# FanRegulator.net
KiCad netlist of a schematic drawn in EAGLE
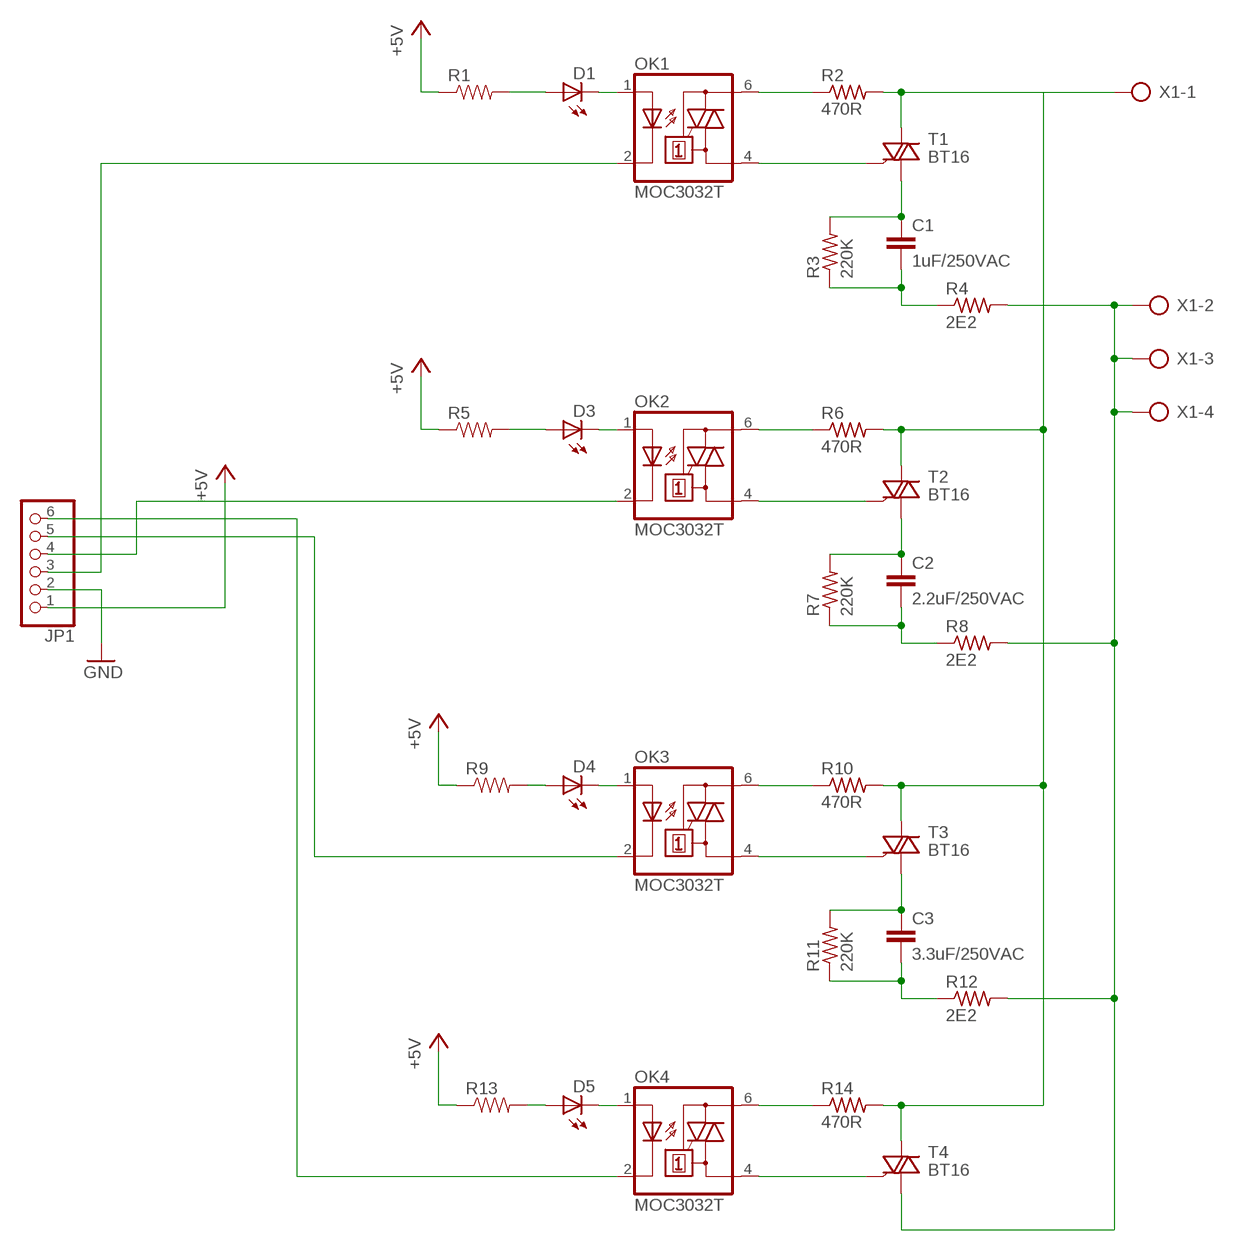
[diagram p0: schematic, sheet 1]

(export (version "E")
  (design (tool "Eeschema 10.0.6"))
  (components
    (comp (ref "C1")
      (value "1uF/250VAC")
      (footprint "eagle-import:C27.5B9")
      (libsource (lib "eagle-import") (part "C27/9"))
    )
    (comp (ref "C2")
      (value "2.2uF/250VAC")
      (footprint "eagle-import:C27.5B9")
      (libsource (lib "eagle-import") (part "C27/9"))
    )
    (comp (ref "C3")
      (value "3.3uF/250VAC")
      (footprint "eagle-import:C27.5B9")
      (libsource (lib "eagle-import") (part "C27/9"))
    )
    (comp (ref "D1")
      (value "LED3MM")
      (footprint "eagle-import:LED3MM")
      (libsource (lib "eagle-import") (part "LED3MM"))
    )
    (comp (ref "D3")
      (value "LED3MM")
      (footprint "eagle-import:LED3MM")
      (libsource (lib "eagle-import") (part "LED3MM"))
    )
    (comp (ref "D4")
      (value "LED3MM")
      (footprint "eagle-import:LED3MM")
      (libsource (lib "eagle-import") (part "LED3MM"))
    )
    (comp (ref "D5")
      (value "LED3MM")
      (footprint "eagle-import:LED3MM")
      (libsource (lib "eagle-import") (part "LED3MM"))
    )
    (comp (ref "JP1")
      (value "PINHD-1X6")
      (footprint "eagle-import:1X06")
      (libsource (lib "eagle-import") (part "PINHD-1X6"))
    )
    (comp (ref "OK1")
      (value "MOC3032T")
      (footprint "eagle-import:DIL06B")
      (libsource (lib "eagle-import") (part "MOC30T32"))
    )
    (comp (ref "OK2")
      (value "MOC3032T")
      (footprint "eagle-import:DIL06B")
      (libsource (lib "eagle-import") (part "MOC30T32"))
    )
    (comp (ref "OK3")
      (value "MOC3032T")
      (footprint "eagle-import:DIL06B")
      (libsource (lib "eagle-import") (part "MOC30T32"))
    )
    (comp (ref "OK4")
      (value "MOC3032T")
      (footprint "eagle-import:DIL06B")
      (libsource (lib "eagle-import") (part "MOC30T32"))
    )
    (comp (ref "R1")
      (value "RESISTOR1206")
      (footprint "eagle-import:1206")
      (libsource (lib "eagle-import") (part "RESISTOR1206"))
    )
    (comp (ref "R2")
      (value "470R")
      (footprint "eagle-import:R0207_1V")
      (libsource (lib "eagle-import") (part "6MM.1"))
    )
    (comp (ref "R3")
      (value "220K")
      (footprint "eagle-import:R0207_1V")
      (libsource (lib "eagle-import") (part "6MM.1"))
    )
    (comp (ref "R4")
      (value "2E2")
      (footprint "eagle-import:R0207_1V")
      (libsource (lib "eagle-import") (part "6MM.1"))
    )
    (comp (ref "R5")
      (value "RESISTOR1206")
      (footprint "eagle-import:1206")
      (libsource (lib "eagle-import") (part "RESISTOR1206"))
    )
    (comp (ref "R6")
      (value "470R")
      (footprint "eagle-import:R0207_1V")
      (libsource (lib "eagle-import") (part "6MM.1"))
    )
    (comp (ref "R7")
      (value "220K")
      (footprint "eagle-import:R0207_1V")
      (libsource (lib "eagle-import") (part "6MM.1"))
    )
    (comp (ref "R8")
      (value "2E2")
      (footprint "eagle-import:R0207_1V")
      (libsource (lib "eagle-import") (part "6MM.1"))
    )
    (comp (ref "R9")
      (value "RESISTOR1206")
      (footprint "eagle-import:1206")
      (libsource (lib "eagle-import") (part "RESISTOR1206"))
    )
    (comp (ref "R10")
      (value "470R")
      (footprint "eagle-import:R0207_1V")
      (libsource (lib "eagle-import") (part "6MM.1"))
    )
    (comp (ref "R11")
      (value "220K")
      (footprint "eagle-import:R0207_1V")
      (libsource (lib "eagle-import") (part "6MM.1"))
    )
    (comp (ref "R12")
      (value "2E2")
      (footprint "eagle-import:R0207_1V")
      (libsource (lib "eagle-import") (part "6MM.1"))
    )
    (comp (ref "R13")
      (value "RESISTOR1206")
      (footprint "eagle-import:1206")
      (libsource (lib "eagle-import") (part "RESISTOR1206"))
    )
    (comp (ref "R14")
      (value "470R")
      (footprint "eagle-import:R0207_1V")
      (libsource (lib "eagle-import") (part "6MM.1"))
    )
    (comp (ref "T1")
      (value "BT16")
      (footprint "eagle-import:TO220BV")
      (libsource (lib "eagle-import") (part "BT138-V"))
    )
    (comp (ref "T2")
      (value "BT16")
      (footprint "eagle-import:TO220BV")
      (libsource (lib "eagle-import") (part "BT138-V"))
    )
    (comp (ref "T3")
      (value "BT16")
      (footprint "eagle-import:TO220BV")
      (libsource (lib "eagle-import") (part "BT138-V"))
    )
    (comp (ref "T4")
      (value "BT16")
      (footprint "eagle-import:TO220BV")
      (libsource (lib "eagle-import") (part "BT138-V"))
    )
    (comp (ref "X1")
      (value "AK300/4")
      (footprint "eagle-import:AK300_4")
      (libsource (lib "eagle-import") (part "AK300/4"))
    )
  )
  (nets
    (net (code "1") (name "+5V") (class "Default")
      (node (ref "JP1") (pin "1") (pinfunction "1_1") (pintype "passive"))
      (node (ref "R1") (pin "1") (pinfunction "1_1") (pintype "passive"))
      (node (ref "R13") (pin "1") (pinfunction "1_1") (pintype "passive"))
      (node (ref "R5") (pin "1") (pinfunction "1_1") (pintype "passive"))
      (node (ref "R9") (pin "1") (pinfunction "1_1") (pintype "passive"))
    )
    (net (code "2") (name "GND") (class "Default")
      (node (ref "JP1") (pin "2") (pinfunction "2_2") (pintype "passive"))
    )
    (net (code "3") (name "Net-(C1-Pad2)") (class "Default")
      (node (ref "C1") (pin "2") (pinfunction "2_2") (pintype "passive"))
      (node (ref "R3") (pin "1") (pinfunction "1_1") (pintype "passive"))
      (node (ref "R4") (pin "1") (pinfunction "1_1") (pintype "passive"))
    )
    (net (code "4") (name "Net-(C2-Pad2)") (class "Default")
      (node (ref "C2") (pin "2") (pinfunction "2_2") (pintype "passive"))
      (node (ref "R7") (pin "1") (pinfunction "1_1") (pintype "passive"))
      (node (ref "R8") (pin "1") (pinfunction "1_1") (pintype "passive"))
    )
    (net (code "5") (name "Net-(C3-Pad2)") (class "Default")
      (node (ref "C3") (pin "2") (pinfunction "2_2") (pintype "passive"))
      (node (ref "R11") (pin "1") (pinfunction "1_1") (pintype "passive"))
      (node (ref "R12") (pin "1") (pinfunction "1_1") (pintype "passive"))
    )
    (net (code "6") (name "Net-(D1-C)") (class "Default")
      (node (ref "D1") (pin "K") (pinfunction "C_K") (pintype "passive"))
      (node (ref "OK1") (pin "1") (pinfunction "A_1") (pintype "passive"))
    )
    (net (code "7") (name "Net-(D1-PadA)") (class "Default")
      (node (ref "D1") (pin "A") (pinfunction "A_A") (pintype "passive"))
      (node (ref "R1") (pin "2") (pinfunction "2_2") (pintype "passive"))
    )
    (net (code "8") (name "Net-(D3-C)") (class "Default")
      (node (ref "D3") (pin "K") (pinfunction "C_K") (pintype "passive"))
      (node (ref "OK2") (pin "1") (pinfunction "A_1") (pintype "passive"))
    )
    (net (code "9") (name "Net-(D3-PadA)") (class "Default")
      (node (ref "D3") (pin "A") (pinfunction "A_A") (pintype "passive"))
      (node (ref "R5") (pin "2") (pinfunction "2_2") (pintype "passive"))
    )
    (net (code "10") (name "Net-(D4-C)") (class "Default")
      (node (ref "D4") (pin "K") (pinfunction "C_K") (pintype "passive"))
      (node (ref "OK3") (pin "1") (pinfunction "A_1") (pintype "passive"))
    )
    (net (code "11") (name "Net-(D4-PadA)") (class "Default")
      (node (ref "D4") (pin "A") (pinfunction "A_A") (pintype "passive"))
      (node (ref "R9") (pin "2") (pinfunction "2_2") (pintype "passive"))
    )
    (net (code "12") (name "Net-(D5-C)") (class "Default")
      (node (ref "D5") (pin "K") (pinfunction "C_K") (pintype "passive"))
      (node (ref "OK4") (pin "1") (pinfunction "A_1") (pintype "passive"))
    )
    (net (code "13") (name "Net-(D5-PadA)") (class "Default")
      (node (ref "D5") (pin "A") (pinfunction "A_A") (pintype "passive"))
      (node (ref "R13") (pin "2") (pinfunction "2_2") (pintype "passive"))
    )
    (net (code "14") (name "Net-(OK1-A1)") (class "Default")
      (node (ref "OK1") (pin "4") (pinfunction "A1_4") (pintype "passive"))
      (node (ref "T1") (pin "G") (pinfunction "G_G") (pintype "passive"))
    )
    (net (code "15") (name "Net-(OK1-A2)") (class "Default")
      (node (ref "OK1") (pin "6") (pinfunction "A2_6") (pintype "passive"))
      (node (ref "R2") (pin "1") (pinfunction "1_1") (pintype "passive"))
    )
    (net (code "16") (name "Net-(OK1-C)") (class "Default")
      (node (ref "JP1") (pin "3") (pinfunction "3_3") (pintype "passive"))
      (node (ref "OK1") (pin "2") (pinfunction "C_2") (pintype "passive"))
    )
    (net (code "17") (name "Net-(OK2-A1)") (class "Default")
      (node (ref "OK2") (pin "4") (pinfunction "A1_4") (pintype "passive"))
      (node (ref "T2") (pin "G") (pinfunction "G_G") (pintype "passive"))
    )
    (net (code "18") (name "Net-(OK2-A2)") (class "Default")
      (node (ref "OK2") (pin "6") (pinfunction "A2_6") (pintype "passive"))
      (node (ref "R6") (pin "1") (pinfunction "1_1") (pintype "passive"))
    )
    (net (code "19") (name "Net-(OK2-C)") (class "Default")
      (node (ref "JP1") (pin "4") (pinfunction "4_4") (pintype "passive"))
      (node (ref "OK2") (pin "2") (pinfunction "C_2") (pintype "passive"))
    )
    (net (code "20") (name "Net-(OK3-A1)") (class "Default")
      (node (ref "OK3") (pin "4") (pinfunction "A1_4") (pintype "passive"))
      (node (ref "T3") (pin "G") (pinfunction "G_G") (pintype "passive"))
    )
    (net (code "21") (name "Net-(OK3-A2)") (class "Default")
      (node (ref "OK3") (pin "6") (pinfunction "A2_6") (pintype "passive"))
      (node (ref "R10") (pin "1") (pinfunction "1_1") (pintype "passive"))
    )
    (net (code "22") (name "Net-(OK3-C)") (class "Default")
      (node (ref "JP1") (pin "5") (pinfunction "5_5") (pintype "passive"))
      (node (ref "OK3") (pin "2") (pinfunction "C_2") (pintype "passive"))
    )
    (net (code "23") (name "Net-(OK4-A1)") (class "Default")
      (node (ref "OK4") (pin "4") (pinfunction "A1_4") (pintype "passive"))
      (node (ref "T4") (pin "G") (pinfunction "G_G") (pintype "passive"))
    )
    (net (code "24") (name "Net-(OK4-A2)") (class "Default")
      (node (ref "OK4") (pin "6") (pinfunction "A2_6") (pintype "passive"))
      (node (ref "R14") (pin "1") (pinfunction "1_1") (pintype "passive"))
    )
    (net (code "25") (name "Net-(OK4-C)") (class "Default")
      (node (ref "JP1") (pin "6") (pinfunction "6_6") (pintype "passive"))
      (node (ref "OK4") (pin "2") (pinfunction "C_2") (pintype "passive"))
    )
    (net (code "26") (name "Net-(T1-A1)") (class "Default")
      (node (ref "C1") (pin "1") (pinfunction "1_1") (pintype "passive"))
      (node (ref "R3") (pin "2") (pinfunction "2_2") (pintype "passive"))
      (node (ref "T1") (pin "T1") (pinfunction "A1_T1") (pintype "passive"))
    )
    (net (code "27") (name "Net-(T1-A2)") (class "Default")
      (node (ref "R10") (pin "2") (pinfunction "2_2") (pintype "passive"))
      (node (ref "R14") (pin "2") (pinfunction "2_2") (pintype "passive"))
      (node (ref "R2") (pin "2") (pinfunction "2_2") (pintype "passive"))
      (node (ref "R6") (pin "2") (pinfunction "2_2") (pintype "passive"))
      (node (ref "T1") (pin "T2") (pinfunction "A2_T2") (pintype "passive"))
      (node (ref "T2") (pin "T2") (pinfunction "A2_T2") (pintype "passive"))
      (node (ref "T3") (pin "T2") (pinfunction "A2_T2") (pintype "passive"))
      (node (ref "T4") (pin "T2") (pinfunction "A2_T2") (pintype "passive"))
      (node (ref "X1") (pin "1") (pinfunction "KL_1") (pintype "passive"))
    )
    (net (code "28") (name "Net-(T2-A1)") (class "Default")
      (node (ref "C2") (pin "1") (pinfunction "1_1") (pintype "passive"))
      (node (ref "R7") (pin "2") (pinfunction "2_2") (pintype "passive"))
      (node (ref "T2") (pin "T1") (pinfunction "A1_T1") (pintype "passive"))
    )
    (net (code "29") (name "Net-(T3-A1)") (class "Default")
      (node (ref "C3") (pin "1") (pinfunction "1_1") (pintype "passive"))
      (node (ref "R11") (pin "2") (pinfunction "2_2") (pintype "passive"))
      (node (ref "T3") (pin "T1") (pinfunction "A1_T1") (pintype "passive"))
    )
    (net (code "30") (name "Net-(T4-A1)") (class "Default")
      (node (ref "R12") (pin "2") (pinfunction "2_2") (pintype "passive"))
      (node (ref "R4") (pin "2") (pinfunction "2_2") (pintype "passive"))
      (node (ref "R8") (pin "2") (pinfunction "2_2") (pintype "passive"))
      (node (ref "T4") (pin "T1") (pinfunction "A1_T1") (pintype "passive"))
      (node (ref "X1") (pin "2") (pinfunction "KL_2") (pintype "passive"))
      (node (ref "X1") (pin "3") (pinfunction "KL_3") (pintype "passive"))
      (node (ref "X1") (pin "4") (pinfunction "KL_4") (pintype "passive"))
    )
  )
)
